# test-conversion.net
KiCad netlist of a schematic drawn in EAGLE
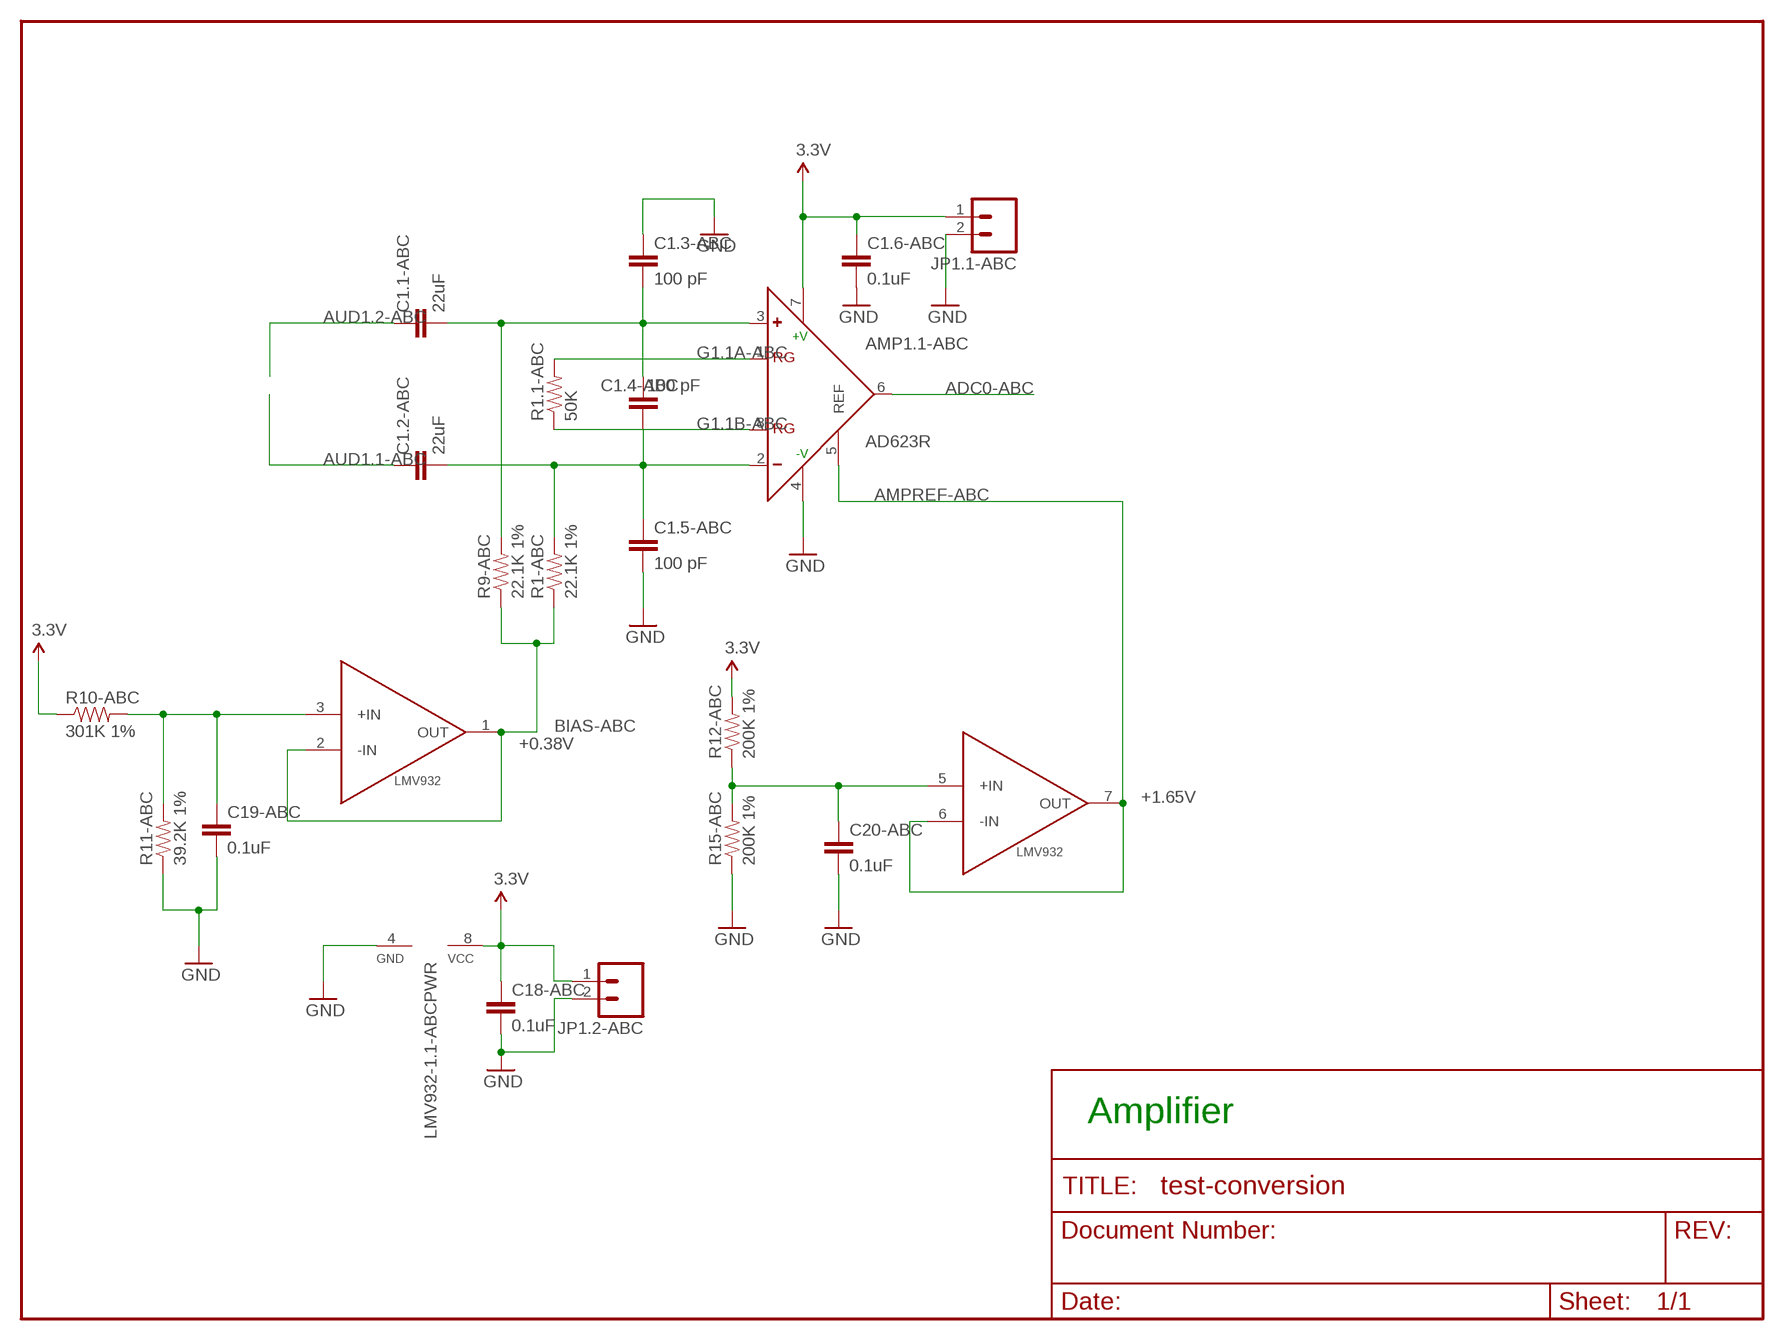
[diagram p0: schematic, sheet 1]

(export (version "E")
  (design (tool "Eeschema 10.0.6"))
  (components
    (comp (ref "AMP1.1-ABC")
      (value "AD623R")
      (footprint "eagle-import:SO8")
      (fields (field (name "MPN") "AD623ARZ."))
      (libsource (lib "eagle-import") (part "AD623R"))
    )
    (comp (ref "C1.1-ABC")
      (value "22uF")
      (footprint "eagle-import:1206")
      (libsource (lib "eagle-import") (part "CAP1206"))
    )
    (comp (ref "C1.2-ABC")
      (value "22uF")
      (footprint "eagle-import:1206")
      (libsource (lib "eagle-import") (part "CAP1206"))
    )
    (comp (ref "C1.3-ABC")
      (value "100 pF")
      (footprint "eagle-import:0805")
      (libsource (lib "eagle-import") (part "CAP0805"))
    )
    (comp (ref "C1.4-ABC")
      (value "100 pF")
      (footprint "eagle-import:0805")
      (libsource (lib "eagle-import") (part "CAP0805"))
    )
    (comp (ref "C1.5-ABC")
      (value "100 pF")
      (footprint "eagle-import:0805")
      (libsource (lib "eagle-import") (part "CAP0805"))
    )
    (comp (ref "C1.6-ABC")
      (value "0.1uF")
      (footprint "eagle-import:0805")
      (libsource (lib "eagle-import") (part "CAP0805"))
    )
    (comp (ref "C18-ABC")
      (value "0.1uF")
      (footprint "eagle-import:0805")
      (libsource (lib "eagle-import") (part "CAP0805"))
    )
    (comp (ref "C19-ABC")
      (value "0.1uF")
      (footprint "eagle-import:0805")
      (libsource (lib "eagle-import") (part "CAP0805"))
    )
    (comp (ref "C20-ABC")
      (value "0.1uF")
      (footprint "eagle-import:0805")
      (libsource (lib "eagle-import") (part "CAP0805"))
    )
    (comp (ref "JP1.1-ABC")
      (value "M021X02_NO_SILK")
      (footprint "eagle-import:1X02_NO_SILK")
      (libsource (lib "eagle-import") (part "M021X02_NO_SILK"))
    )
    (comp (ref "JP1.2-ABC")
      (value "M021X02_NO_SILK")
      (footprint "eagle-import:1X02_NO_SILK")
      (libsource (lib "eagle-import") (part "M021X02_NO_SILK"))
    )
    (comp (ref "LMV932-1.1-ABC")
      (value "LMV932")
      (footprint "eagle-import:SOIC8")
      (libsource (lib "eagle-import") (part "LMV932"))
    )
    (comp (ref "R1-ABC")
      (value "22.1K 1%")
      (footprint "eagle-import:0805")
      (libsource (lib "eagle-import") (part "RESISTOR0805-RES"))
    )
    (comp (ref "R1.1-ABC")
      (value "50K")
      (footprint "eagle-import:0805")
      (libsource (lib "eagle-import") (part "SparkFun-Passives_RESISTOR0805-RES"))
    )
    (comp (ref "R9-ABC")
      (value "22.1K 1%")
      (footprint "eagle-import:0805")
      (libsource (lib "eagle-import") (part "RESISTOR0805-RES"))
    )
    (comp (ref "R10-ABC")
      (value "301K 1%")
      (footprint "eagle-import:0805")
      (libsource (lib "eagle-import") (part "RESISTOR0805-RES"))
    )
    (comp (ref "R11-ABC")
      (value "39.2K 1%")
      (footprint "eagle-import:0805")
      (libsource (lib "eagle-import") (part "RESISTOR0805-RES"))
    )
    (comp (ref "R12-ABC")
      (value "200K 1%")
      (footprint "eagle-import:0805")
      (libsource (lib "eagle-import") (part "RESISTOR0805-RES"))
    )
    (comp (ref "R15-ABC")
      (value "200K 1%")
      (footprint "eagle-import:0805")
      (libsource (lib "eagle-import") (part "RESISTOR0805-RES"))
    )
  )
  (nets
    (net (code "1") (name "/ADC0-ABC") (class "Default")
      (node (ref "AMP1.1-ABC") (pin "6") (pinfunction "OUT_6") (pintype "output"))
    )
    (net (code "2") (name "/AMPREF-ABC") (class "Default")
      (node (ref "AMP1.1-ABC") (pin "5") (pinfunction "REF_5") (pintype "passive"))
      (node (ref "LMV932-1.1-ABC") (pin "6") (pinfunction "-IN_6") (pintype "input"))
      (node (ref "LMV932-1.1-ABC") (pin "7") (pinfunction "OUT_7") (pintype "output"))
    )
    (net (code "3") (name "/AUD1.1-ABC") (class "Default")
      (node (ref "C1.2-ABC") (pin "1") (pinfunction "1_1") (pintype "passive"))
    )
    (net (code "4") (name "/AUD1.2-ABC") (class "Default")
      (node (ref "C1.1-ABC") (pin "1") (pinfunction "1_1") (pintype "passive"))
    )
    (net (code "5") (name "/BIAS-ABC") (class "Default")
      (node (ref "LMV932-1.1-ABC") (pin "1") (pinfunction "OUT_1") (pintype "output"))
      (node (ref "LMV932-1.1-ABC") (pin "2") (pinfunction "-IN_2") (pintype "input"))
      (node (ref "R1-ABC") (pin "1") (pinfunction "1_1") (pintype "passive"))
      (node (ref "R9-ABC") (pin "1") (pinfunction "1_1") (pintype "passive"))
    )
    (net (code "6") (name "/G1.1A-ABC") (class "Default")
      (node (ref "AMP1.1-ABC") (pin "1") (pinfunction "RG_1") (pintype "passive"))
      (node (ref "R1.1-ABC") (pin "2") (pinfunction "2_2") (pintype "passive"))
    )
    (net (code "7") (name "/G1.1B-ABC") (class "Default")
      (node (ref "AMP1.1-ABC") (pin "8") (pinfunction "RG_8") (pintype "passive"))
      (node (ref "R1.1-ABC") (pin "1") (pinfunction "1_1") (pintype "passive"))
    )
    (net (code "8") (name "3.3V") (class "Default")
      (node (ref "AMP1.1-ABC") (pin "7") (pinfunction "+V_7") (pintype "power_in"))
      (node (ref "C1.6-ABC") (pin "1") (pinfunction "1_1") (pintype "passive"))
      (node (ref "C18-ABC") (pin "1") (pinfunction "1_1") (pintype "passive"))
      (node (ref "JP1.1-ABC") (pin "1") (pinfunction "1_1") (pintype "passive"))
      (node (ref "JP1.2-ABC") (pin "1") (pinfunction "1_1") (pintype "passive"))
      (node (ref "LMV932-1.1-ABC") (pin "8") (pinfunction "VCC_8") (pintype "power_in"))
      (node (ref "R10-ABC") (pin "1") (pinfunction "1_1") (pintype "passive"))
      (node (ref "R12-ABC") (pin "2") (pinfunction "2_2") (pintype "passive"))
    )
    (net (code "9") (name "GND") (class "Default")
      (node (ref "AMP1.1-ABC") (pin "4") (pinfunction "-V_4") (pintype "power_in"))
      (node (ref "C1.3-ABC") (pin "1") (pinfunction "1_1") (pintype "passive"))
      (node (ref "C1.5-ABC") (pin "2") (pinfunction "2_2") (pintype "passive"))
      (node (ref "C1.6-ABC") (pin "2") (pinfunction "2_2") (pintype "passive"))
      (node (ref "C18-ABC") (pin "2") (pinfunction "2_2") (pintype "passive"))
      (node (ref "C19-ABC") (pin "2") (pinfunction "2_2") (pintype "passive"))
      (node (ref "C20-ABC") (pin "2") (pinfunction "2_2") (pintype "passive"))
      (node (ref "JP1.1-ABC") (pin "2") (pinfunction "2_2") (pintype "passive"))
      (node (ref "JP1.2-ABC") (pin "2") (pinfunction "2_2") (pintype "passive"))
      (node (ref "LMV932-1.1-ABC") (pin "4") (pinfunction "GND_4") (pintype "power_in"))
      (node (ref "R11-ABC") (pin "1") (pinfunction "1_1") (pintype "passive"))
      (node (ref "R15-ABC") (pin "1") (pinfunction "1_1") (pintype "passive"))
    )
    (net (code "10") (name "Net-(AMP1.1-ABC-+)") (class "Default")
      (node (ref "AMP1.1-ABC") (pin "3") (pinfunction "+_3") (pintype "input"))
      (node (ref "C1.1-ABC") (pin "2") (pinfunction "2_2") (pintype "passive"))
      (node (ref "C1.3-ABC") (pin "2") (pinfunction "2_2") (pintype "passive"))
      (node (ref "C1.4-ABC") (pin "1") (pinfunction "1_1") (pintype "passive"))
      (node (ref "R9-ABC") (pin "2") (pinfunction "2_2") (pintype "passive"))
    )
    (net (code "11") (name "Net-(AMP1.1-ABC--)") (class "Default")
      (node (ref "AMP1.1-ABC") (pin "2") (pinfunction "-_2") (pintype "input"))
      (node (ref "C1.2-ABC") (pin "2") (pinfunction "2_2") (pintype "passive"))
      (node (ref "C1.4-ABC") (pin "2") (pinfunction "2_2") (pintype "passive"))
      (node (ref "C1.5-ABC") (pin "1") (pinfunction "1_1") (pintype "passive"))
      (node (ref "R1-ABC") (pin "2") (pinfunction "2_2") (pintype "passive"))
    )
    (net (code "12") (name "Net-(LMV932-1.1-ABCA-+IN)") (class "Default")
      (node (ref "C19-ABC") (pin "1") (pinfunction "1_1") (pintype "passive"))
      (node (ref "LMV932-1.1-ABC") (pin "3") (pinfunction "+IN_3") (pintype "input"))
      (node (ref "R10-ABC") (pin "2") (pinfunction "2_2") (pintype "passive"))
      (node (ref "R11-ABC") (pin "2") (pinfunction "2_2") (pintype "passive"))
    )
    (net (code "13") (name "Net-(LMV932-1.1-ABCB-+IN)") (class "Default")
      (node (ref "C20-ABC") (pin "1") (pinfunction "1_1") (pintype "passive"))
      (node (ref "LMV932-1.1-ABC") (pin "5") (pinfunction "+IN_5") (pintype "input"))
      (node (ref "R12-ABC") (pin "1") (pinfunction "1_1") (pintype "passive"))
      (node (ref "R15-ABC") (pin "2") (pinfunction "2_2") (pintype "passive"))
    )
  )
)
